# ToolChanger_ConnexionBoard.net
KiCad netlist of a schematic drawn in EAGLE
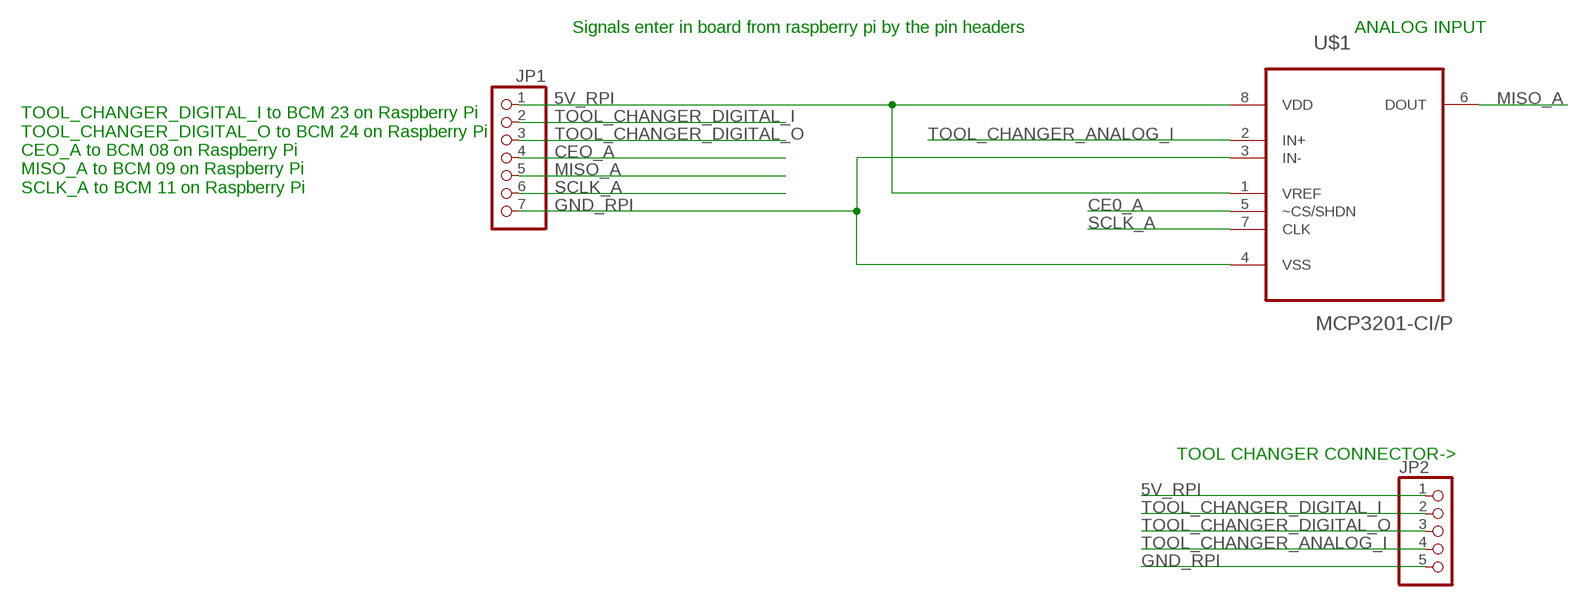
[diagram p0: schematic, sheet 1]

(export (version "E")
  (design (tool "Eeschema 10.0.6"))
  (components
    (comp (ref "JP1")
      (value "PINHD-1X7")
      (footprint "eagle-import:1X07")
      (libsource (lib "eagle-import") (part "PINHD-1X7"))
    )
    (comp (ref "JP2")
      (value "PINHD-1X5")
      (footprint "eagle-import:1X05")
      (libsource (lib "eagle-import") (part "PINHD-1X5"))
    )
    (comp (ref "U$1")
      (value "MCP3201-CI/P")
      (footprint "eagle-import:DIP254P762X533-8")
      (fields (field (name "MF") "Microchip"))
      (libsource (lib "eagle-import") (part "MCP3201-CI/P"))
    )
  )
  (nets
    (net (code "1") (name "/5V_RPI") (class "Default")
      (node (ref "JP1") (pin "1") (pinfunction "1_1") (pintype "passive"))
      (node (ref "JP2") (pin "1") (pinfunction "1_1") (pintype "passive"))
      (node (ref "U$1") (pin "1") (pinfunction "VREF_1") (pintype "input"))
      (node (ref "U$1") (pin "8") (pinfunction "VDD_8") (pintype "power_in"))
    )
    (net (code "2") (name "/CE0_A") (class "Default")
      (node (ref "U$1") (pin "5") (pinfunction "~{CS/SHDN}_5") (pintype "input"))
    )
    (net (code "3") (name "/CEO_A") (class "Default")
      (node (ref "JP1") (pin "4") (pinfunction "4_4") (pintype "passive"))
    )
    (net (code "4") (name "/GND_RPI") (class "Default")
      (node (ref "JP1") (pin "7") (pinfunction "7_7") (pintype "passive"))
      (node (ref "JP2") (pin "5") (pinfunction "5_5") (pintype "passive"))
      (node (ref "U$1") (pin "3") (pinfunction "IN-_3") (pintype "input"))
      (node (ref "U$1") (pin "4") (pinfunction "VSS_4") (pintype "passive"))
    )
    (net (code "5") (name "/MISO_A") (class "Default")
      (node (ref "JP1") (pin "5") (pinfunction "5_5") (pintype "passive"))
      (node (ref "U$1") (pin "6") (pinfunction "DOUT_6") (pintype "output"))
    )
    (net (code "6") (name "/SCLK_A") (class "Default")
      (node (ref "JP1") (pin "6") (pinfunction "6_6") (pintype "passive"))
      (node (ref "U$1") (pin "7") (pinfunction "CLK_7") (pintype "input"))
    )
    (net (code "7") (name "/TOOL_CHANGER_ANALOG_I") (class "Default")
      (node (ref "JP2") (pin "4") (pinfunction "4_4") (pintype "passive"))
      (node (ref "U$1") (pin "2") (pinfunction "IN+_2") (pintype "input"))
    )
    (net (code "8") (name "/TOOL_CHANGER_DIGITAL_I") (class "Default")
      (node (ref "JP1") (pin "2") (pinfunction "2_2") (pintype "passive"))
      (node (ref "JP2") (pin "2") (pinfunction "2_2") (pintype "passive"))
    )
    (net (code "9") (name "/TOOL_CHANGER_DIGITAL_O") (class "Default")
      (node (ref "JP1") (pin "3") (pinfunction "3_3") (pintype "passive"))
      (node (ref "JP2") (pin "3") (pinfunction "3_3") (pintype "passive"))
    )
  )
)
